# LP_rev1.net
KiCad netlist of a schematic drawn in EAGLE
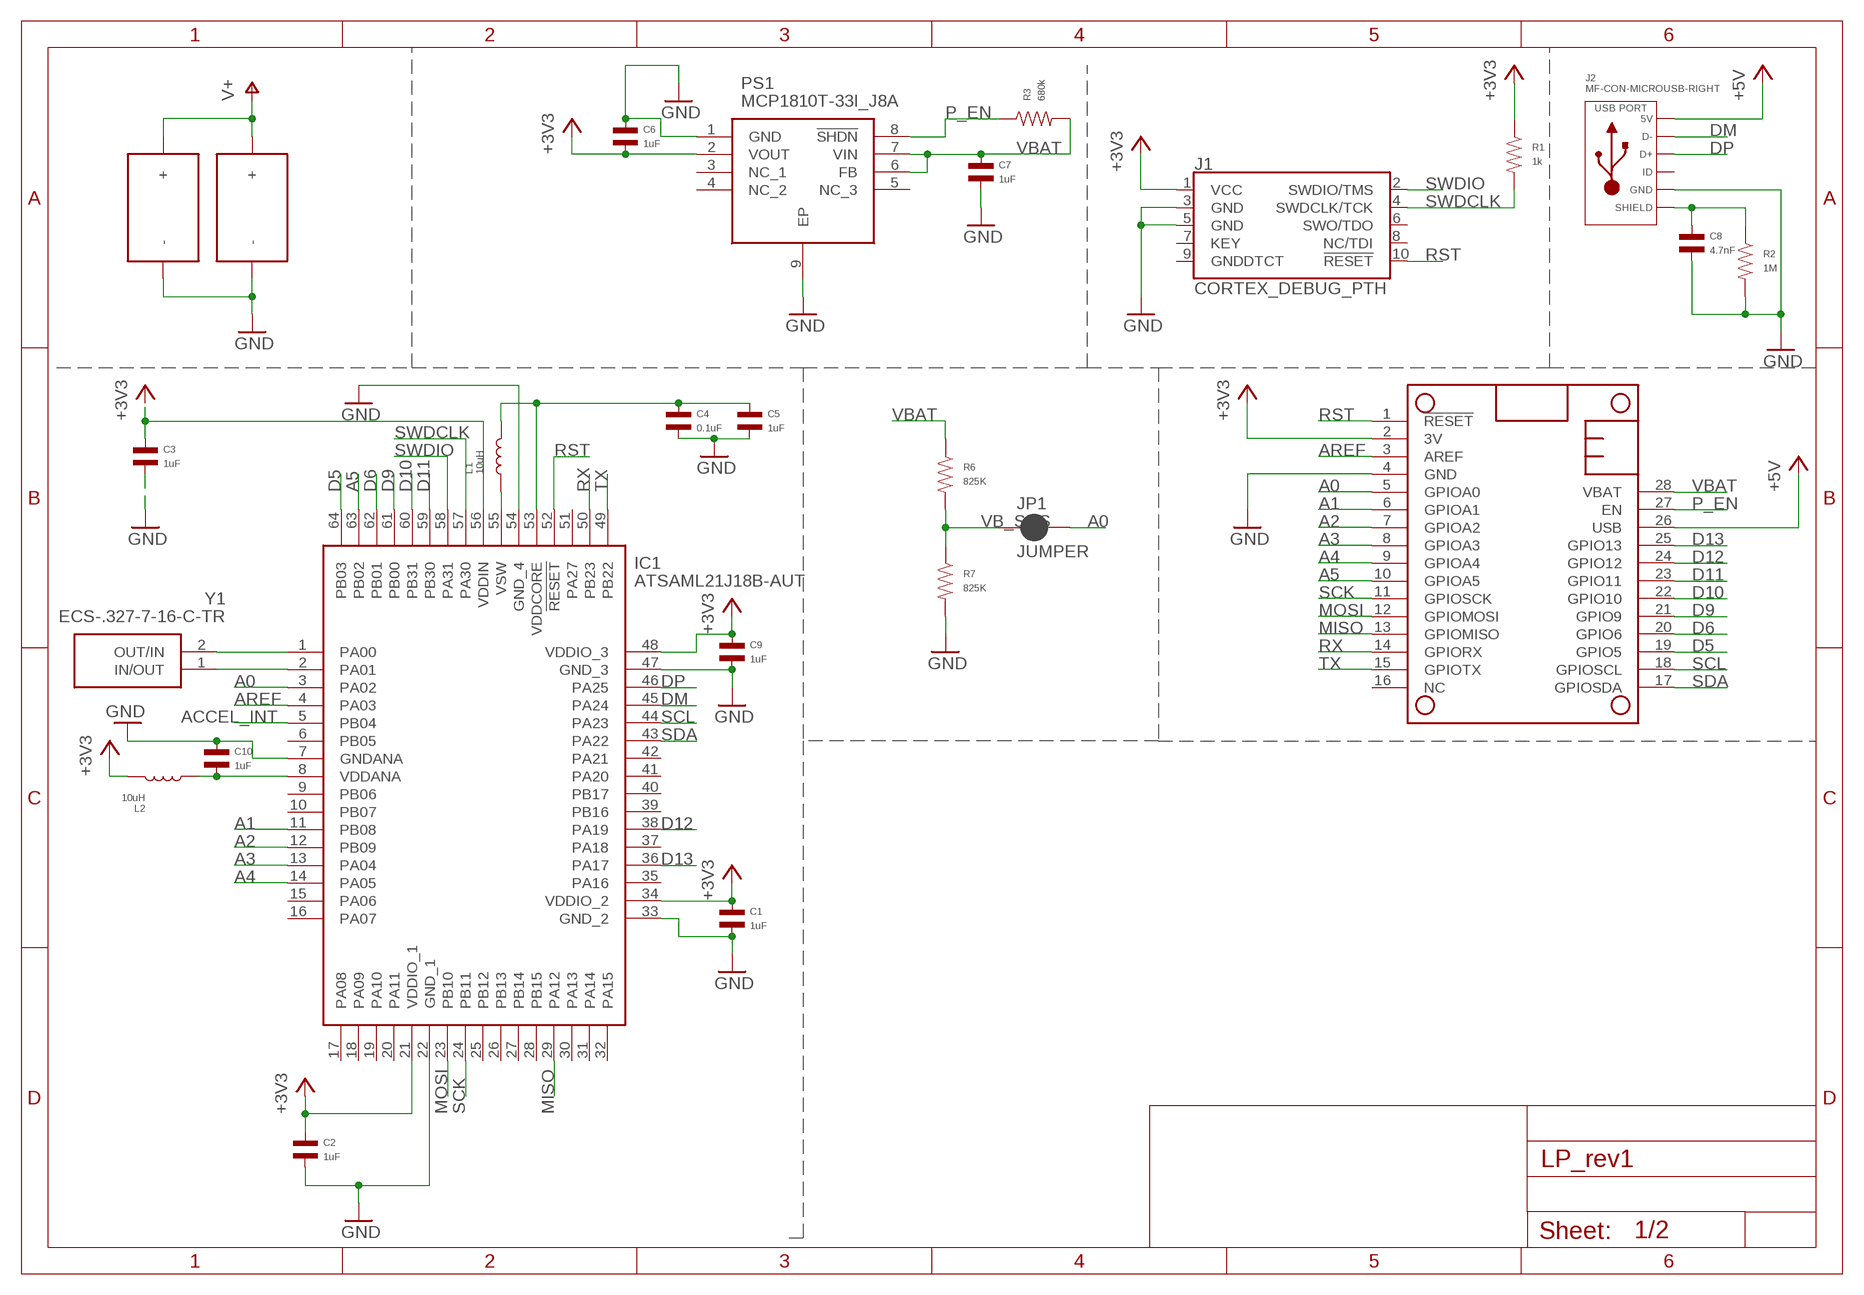
[diagram p0: schematic, sheet 1]
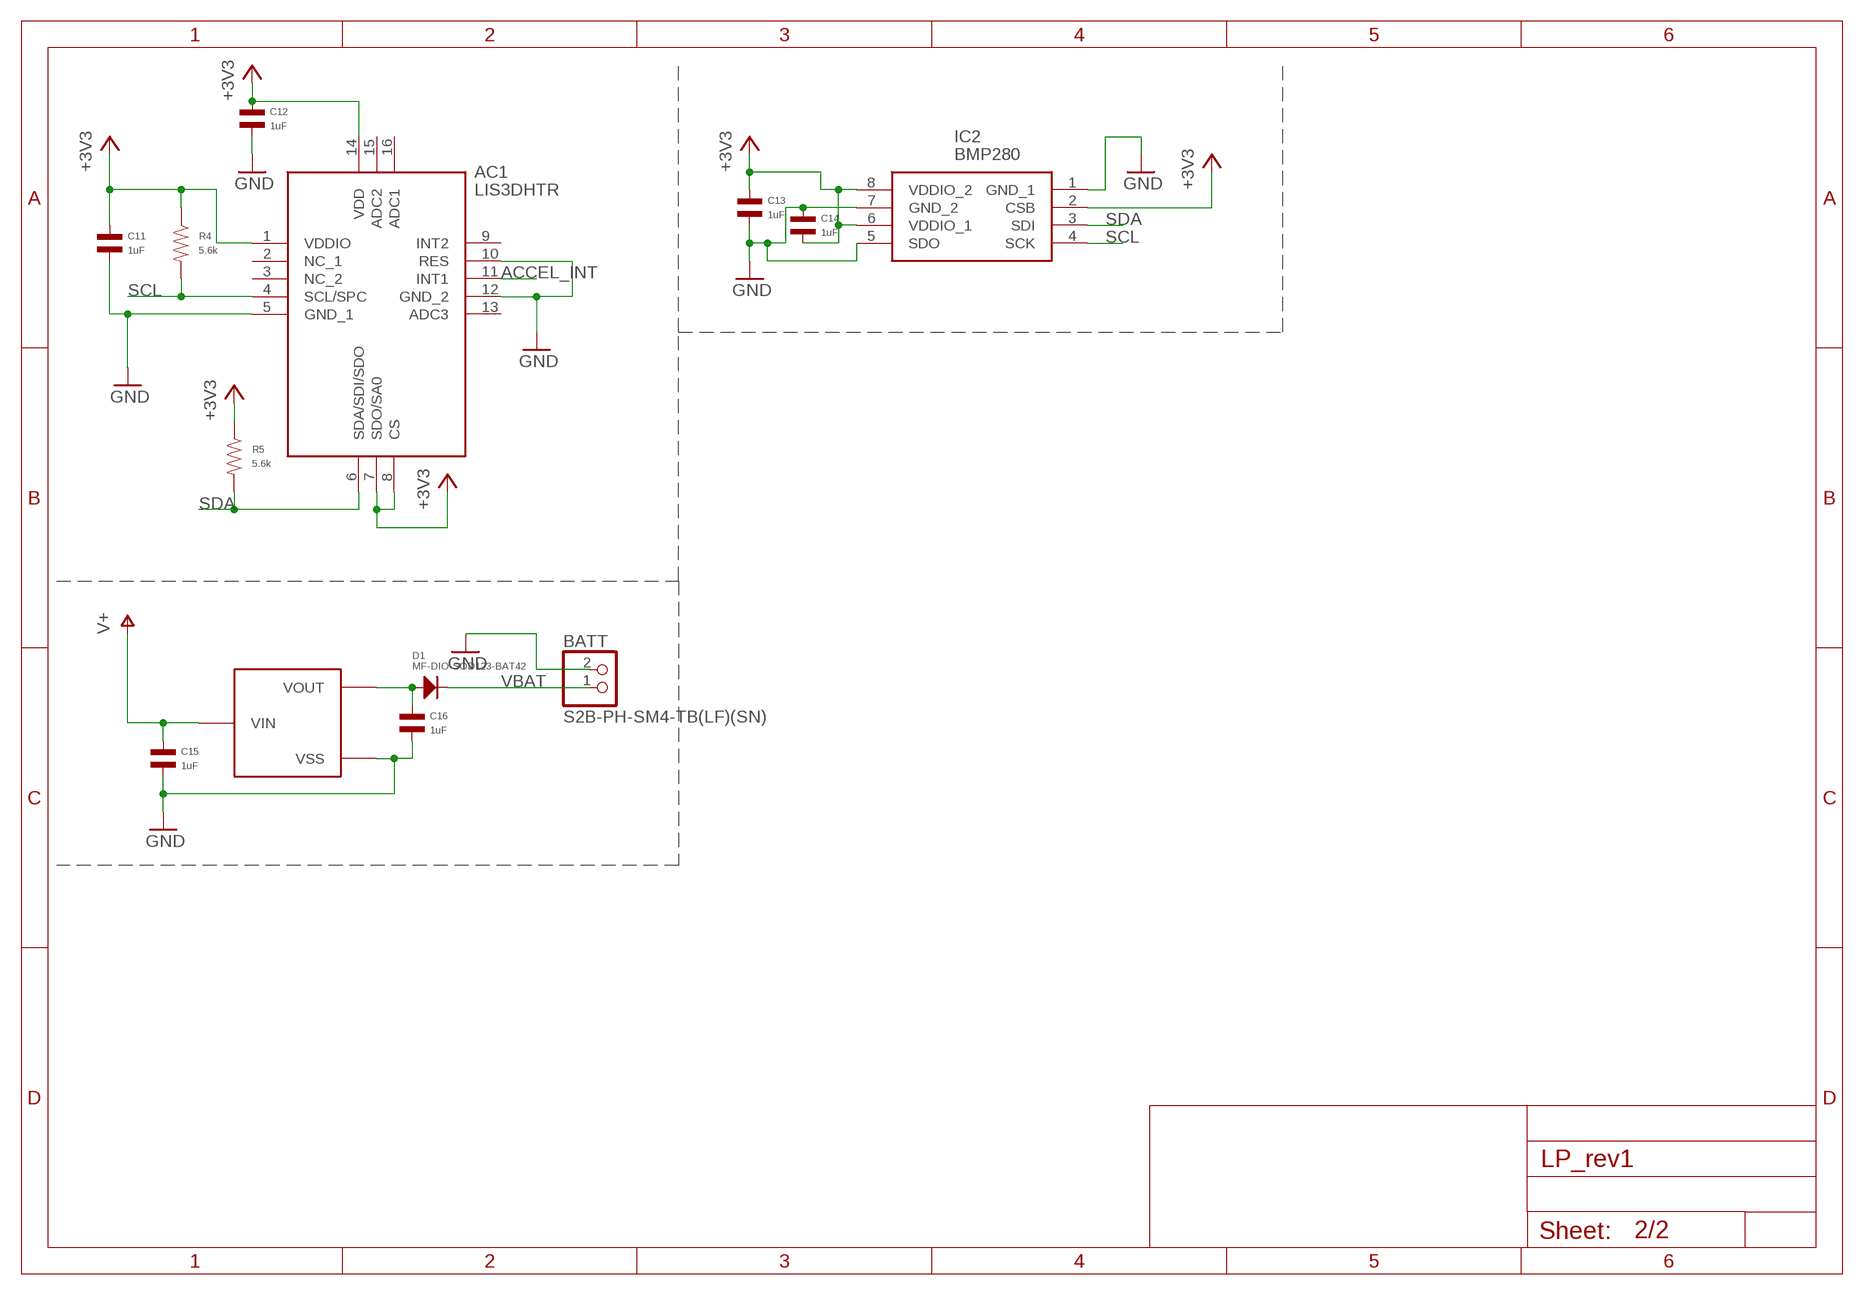
[diagram p1: schematic, sheet 2]

(export (version "E")
  (design (tool "Eeschema 10.0.6"))
  (components
    (comp (ref "AC1")
      (value "LIS3DHTR")
      (footprint "eagle-import:PQFN50P300X300X100-16N")
      (fields (field (name "MOUSER_PART_NUMBER") "511-LIS3DHTR") (field (name "RS_PART_NUMBER") "7931364P"))
      (libsource (lib "eagle-import") (part "LIS3DHTR"))
    )
    (comp (ref "BATT")
      (value "S2B-PH-SM4-TB(LF)(SN)")
      (footprint "eagle-import:JST-PH-2-SMT-RA")
      (libsource (lib "eagle-import") (part "JST_2PIN-SMT-RA"))
    )
    (comp (ref "C11")
      (value "1uF")
      (footprint "eagle-import:C0402")
      (libsource (lib "eagle-import") (part "CAPACITOR_NP_0402"))
    )
    (comp (ref "C12")
      (value "1uF")
      (footprint "eagle-import:C0402")
      (libsource (lib "eagle-import") (part "CAPACITOR_NP_0402"))
    )
    (comp (ref "C13")
      (value "1uF")
      (footprint "eagle-import:C0402")
      (libsource (lib "eagle-import") (part "CAPACITOR_NP_0402"))
    )
    (comp (ref "C14")
      (value "1uF")
      (footprint "eagle-import:C0402")
      (libsource (lib "eagle-import") (part "CAPACITOR_NP_0402"))
    )
    (comp (ref "C15")
      (value "1uF")
      (footprint "eagle-import:C0402")
      (libsource (lib "eagle-import") (part "CAPACITOR_NP_0402"))
    )
    (comp (ref "C16")
      (value "1uF")
      (footprint "eagle-import:C0402")
      (libsource (lib "eagle-import") (part "CAPACITOR_NP_0402"))
    )
    (comp (ref "D1")
      (value "MF-DIO-SOD123-BAT42")
      (footprint "eagle-import:SOD-123")
      (fields (field (name "HOUSEPART") "YES"))
      (libsource (lib "eagle-import") (part "DIODES_SOD-123_BAT42"))
    )
    (comp (ref "IC2")
      (value "BMP280")
      (footprint "eagle-import:8-PIN-METAL-LID-LGA")
      (fields
        (field (name "MANUFACTURER_PART_NUMBER") "bmp280")
        (field (name "MOUSER_PART_NUMBER") "262-BMP280")
      )
      (libsource (lib "eagle-import") (part "BMP280"))
    )
    (comp (ref "R4")
      (value "5.6k")
      (footprint "eagle-import:R0402")
      (libsource (lib "eagle-import") (part "RESISTOR_0402"))
    )
    (comp (ref "R5")
      (value "5.6k")
      (footprint "eagle-import:R0402")
      (libsource (lib "eagle-import") (part "RESISTOR_0402"))
    )
    (comp (ref "U$3")
      (value "XC6206P422MR-G")
      (footprint "eagle-import:XC6206")
      (libsource (lib "eagle-import") (part "XC6206"))
    )
    (comp (ref "C1")
      (value "1uF")
      (footprint "eagle-import:C0402")
      (libsource (lib "eagle-import") (part "CAPACITOR_NP_0402"))
    )
    (comp (ref "C2")
      (value "1uF")
      (footprint "eagle-import:C0402")
      (libsource (lib "eagle-import") (part "CAPACITOR_NP_0402"))
    )
    (comp (ref "C3")
      (value "1uF")
      (footprint "eagle-import:C0402")
      (libsource (lib "eagle-import") (part "CAPACITOR_NP_0402"))
    )
    (comp (ref "C4")
      (value "0.1uF")
      (footprint "eagle-import:C0402")
      (libsource (lib "eagle-import") (part "CAPACITOR_NP_0402"))
    )
    (comp (ref "C5")
      (value "1uF")
      (footprint "eagle-import:C0402")
      (libsource (lib "eagle-import") (part "CAPACITOR_NP_0402"))
    )
    (comp (ref "C6")
      (value "1uF")
      (footprint "eagle-import:C0402")
      (libsource (lib "eagle-import") (part "CAPACITOR_NP_0402"))
    )
    (comp (ref "C7")
      (value "1uF")
      (footprint "eagle-import:C0402")
      (libsource (lib "eagle-import") (part "CAPACITOR_NP_0402"))
    )
    (comp (ref "C8")
      (value "4.7nF")
      (footprint "eagle-import:C0402")
      (libsource (lib "eagle-import") (part "CAPACITOR_NP_0402"))
    )
    (comp (ref "C9")
      (value "1uF")
      (footprint "eagle-import:C0402")
      (libsource (lib "eagle-import") (part "CAPACITOR_NP_0402"))
    )
    (comp (ref "C10")
      (value "1uF")
      (footprint "eagle-import:C0402")
      (libsource (lib "eagle-import") (part "CAPACITOR_NP_0402"))
    )
    (comp (ref "IC1")
      (value "ATSAML21J18B-AUT")
      (footprint "eagle-import:QFP50P1200X1200X120-64N")
      (fields (field (name "MOUSER_PART_NUMBER") "556-ATSAML21J18B-AUT"))
      (libsource (lib "eagle-import") (part "ATSAML21J18B-AUT"))
    )
    (comp (ref "J1")
      (value "CORTEX_DEBUG_PTH")
      (footprint "eagle-import:2X5-PTH-1.27MM")
      (libsource (lib "eagle-import") (part "CORTEX_DEBUG_PTH"))
    )
    (comp (ref "J2")
      (value "MF-CON-MICROUSB-RIGHT")
      (footprint "eagle-import:MICROUSB-RIGHT")
      (fields (field (name "HOUSEPART") "YES"))
      (libsource (lib "eagle-import") (part "USB_MICRO_RIGHT"))
    )
    (comp (ref "JP1")
      (value "JUMPER")
      (footprint "eagle-import:SMT-JUMPER_2_NC_PASTE_NO-SILK")
      (libsource (lib "eagle-import") (part "JUMPER-SMT_2_NC_PASTE_NO-SILK"))
    )
    (comp (ref "L1")
      (value "10uH")
      (footprint "eagle-import:L0603")
      (libsource (lib "eagle-import") (part "INDUCTOR_0603"))
    )
    (comp (ref "L2")
      (value "10uH")
      (footprint "eagle-import:L0603")
      (libsource (lib "eagle-import") (part "INDUCTOR_0603"))
    )
    (comp (ref "MS1")
      (value "FEATHERWING")
      (footprint "eagle-import:FEATHERWING")
      (libsource (lib "eagle-import") (part "FEATHERWING"))
    )
    (comp (ref "PS1")
      (value "MCP1810T-33I_J8A")
      (footprint "eagle-import:SON50P200X200X90-9N")
      (fields
        (field (name "MANUFACTURER_PART_NUMBER") "MCP1810T-33I/J8A")
        (field (name "MOUSER_PART_NUMBER") "579-MCP1810T-33I/J8A")
        (field (name "RS_PART_NUMBER") "1468894P")
      )
      (libsource (lib "eagle-import") (part "MCP1810T-33I_J8A"))
    )
    (comp (ref "R1")
      (value "1k")
      (footprint "eagle-import:R0402")
      (libsource (lib "eagle-import") (part "RESISTOR_0402"))
    )
    (comp (ref "R2")
      (value "1M")
      (footprint "eagle-import:R0402")
      (libsource (lib "eagle-import") (part "RESISTOR_0402"))
    )
    (comp (ref "R3")
      (value "680k")
      (footprint "eagle-import:R0402")
      (libsource (lib "eagle-import") (part "RESISTOR_0402"))
    )
    (comp (ref "R6")
      (value "825K")
      (footprint "eagle-import:R0402")
      (libsource (lib "eagle-import") (part "RESISTOR_0402"))
    )
    (comp (ref "R7")
      (value "825K")
      (footprint "eagle-import:R0402")
      (libsource (lib "eagle-import") (part "RESISTOR_0402"))
    )
    (comp (ref "U$1")
      (value "KXOB25-01X8F")
      (footprint "eagle-import:KXOB25-01X8F")
      (libsource (lib "eagle-import") (part "KXOB25-01X8F"))
    )
    (comp (ref "U$2")
      (value "KXOB25-01X8F")
      (footprint "eagle-import:KXOB25-01X8F")
      (libsource (lib "eagle-import") (part "KXOB25-01X8F"))
    )
    (comp (ref "Y1")
      (value "ECS-.327-7-16-C-TR")
      (footprint "eagle-import:ECS327516TR")
      (fields (field (name "MOUSER_PART_NUMBER") "520-.327-7-16-CT"))
      (libsource (lib "eagle-import") (part "ECS-.327-7-16-C-TR"))
    )
  )
  (nets
    (net (code "1") (name "+3V3") (class "Default")
      (node (ref "AC1") (pin "1") (pinfunction "VDDIO_1") (pintype "power_in"))
      (node (ref "AC1") (pin "14") (pinfunction "VDD_14") (pintype "power_in"))
      (node (ref "AC1") (pin "7") (pinfunction "SDO/SA0_7") (pintype "bidirectional"))
      (node (ref "AC1") (pin "8") (pinfunction "CS_8") (pintype "input"))
      (node (ref "C1") (pin "P$1") (pinfunction "P$1_P$1") (pintype "passive"))
      (node (ref "C11") (pin "P$1") (pinfunction "P$1_P$1") (pintype "passive"))
      (node (ref "C12") (pin "P$1") (pinfunction "P$1_P$1") (pintype "passive"))
      (node (ref "C13") (pin "P$1") (pinfunction "P$1_P$1") (pintype "passive"))
      (node (ref "C14") (pin "P$2") (pinfunction "P$2_P$2") (pintype "passive"))
      (node (ref "C2") (pin "P$1") (pinfunction "P$1_P$1") (pintype "passive"))
      (node (ref "C3") (pin "P$1") (pinfunction "P$1_P$1") (pintype "passive"))
      (node (ref "C6") (pin "P$2") (pinfunction "P$2_P$2") (pintype "passive"))
      (node (ref "C9") (pin "P$1") (pinfunction "P$1_P$1") (pintype "passive"))
      (node (ref "IC1") (pin "21") (pinfunction "VDDIO_1_21") (pintype "bidirectional"))
      (node (ref "IC1") (pin "34") (pinfunction "VDDIO_2_34") (pintype "bidirectional"))
      (node (ref "IC1") (pin "48") (pinfunction "VDDIO_3_48") (pintype "bidirectional"))
      (node (ref "IC1") (pin "56") (pinfunction "VDDIN_56") (pintype "bidirectional"))
      (node (ref "IC2") (pin "2") (pinfunction "CSB_2") (pintype "input"))
      (node (ref "IC2") (pin "6") (pinfunction "VDDIO_1_6") (pintype "power_in"))
      (node (ref "IC2") (pin "8") (pinfunction "VDDIO_2_8") (pintype "power_in"))
      (node (ref "J1") (pin "1") (pinfunction "VCC_1") (pintype "bidirectional"))
      (node (ref "L2") (pin "P$2") (pinfunction "P$2_P$2") (pintype "passive"))
      (node (ref "MS1") (pin "2") (pinfunction "3V_2") (pintype "power_in"))
      (node (ref "PS1") (pin "2") (pinfunction "VOUT_2") (pintype "output"))
      (node (ref "R1") (pin "P$1") (pinfunction "P$1_P$1") (pintype "passive"))
      (node (ref "R4") (pin "P$1") (pinfunction "P$1_P$1") (pintype "passive"))
      (node (ref "R5") (pin "P$1") (pinfunction "P$1_P$1") (pintype "passive"))
    )
    (net (code "2") (name "+5V") (class "Default")
      (node (ref "J2") (pin "1") (pinfunction "5V_1") (pintype "power_in"))
      (node (ref "MS1") (pin "26") (pinfunction "USB_26") (pintype "power_in"))
    )
    (net (code "3") (name "A0") (class "Default")
      (node (ref "IC1") (pin "3") (pinfunction "PA02_3") (pintype "bidirectional"))
      (node (ref "JP1") (pin "2") (pinfunction "2_2") (pintype "passive"))
      (node (ref "MS1") (pin "5") (pinfunction "GPIOA0_5") (pintype "bidirectional"))
    )
    (net (code "4") (name "A1") (class "Default")
      (node (ref "IC1") (pin "11") (pinfunction "PB08_11") (pintype "bidirectional"))
      (node (ref "MS1") (pin "6") (pinfunction "GPIOA1_6") (pintype "bidirectional"))
    )
    (net (code "5") (name "A2") (class "Default")
      (node (ref "IC1") (pin "12") (pinfunction "PB09_12") (pintype "bidirectional"))
      (node (ref "MS1") (pin "7") (pinfunction "GPIOA2_7") (pintype "bidirectional"))
    )
    (net (code "6") (name "A3") (class "Default")
      (node (ref "IC1") (pin "13") (pinfunction "PA04_13") (pintype "bidirectional"))
      (node (ref "MS1") (pin "8") (pinfunction "GPIOA3_8") (pintype "bidirectional"))
    )
    (net (code "7") (name "A4") (class "Default")
      (node (ref "IC1") (pin "14") (pinfunction "PA05_14") (pintype "bidirectional"))
      (node (ref "MS1") (pin "9") (pinfunction "GPIOA4_9") (pintype "bidirectional"))
    )
    (net (code "8") (name "A5") (class "Default")
      (node (ref "IC1") (pin "63") (pinfunction "PB02_63") (pintype "bidirectional"))
      (node (ref "MS1") (pin "10") (pinfunction "GPIOA5_10") (pintype "bidirectional"))
    )
    (net (code "9") (name "ACCEL_INT") (class "Default")
      (node (ref "AC1") (pin "11") (pinfunction "INT1_11") (pintype "input"))
      (node (ref "IC1") (pin "5") (pinfunction "PB04_5") (pintype "bidirectional"))
    )
    (net (code "10") (name "AREF") (class "Default")
      (node (ref "IC1") (pin "4") (pinfunction "PA03_4") (pintype "bidirectional"))
      (node (ref "MS1") (pin "3") (pinfunction "AREF_3") (pintype "passive"))
    )
    (net (code "11") (name "D5") (class "Default")
      (node (ref "IC1") (pin "64") (pinfunction "PB03_64") (pintype "bidirectional"))
      (node (ref "MS1") (pin "19") (pinfunction "GPIO5_19") (pintype "bidirectional"))
    )
    (net (code "12") (name "D6") (class "Default")
      (node (ref "IC1") (pin "62") (pinfunction "PB01_62") (pintype "bidirectional"))
      (node (ref "MS1") (pin "20") (pinfunction "GPIO6_20") (pintype "bidirectional"))
    )
    (net (code "13") (name "D9") (class "Default")
      (node (ref "IC1") (pin "61") (pinfunction "PB00_61") (pintype "bidirectional"))
      (node (ref "MS1") (pin "21") (pinfunction "GPIO9_21") (pintype "bidirectional"))
    )
    (net (code "14") (name "D10") (class "Default")
      (node (ref "IC1") (pin "60") (pinfunction "PB31_60") (pintype "bidirectional"))
      (node (ref "MS1") (pin "22") (pinfunction "GPIO10_22") (pintype "bidirectional"))
    )
    (net (code "15") (name "D11") (class "Default")
      (node (ref "IC1") (pin "59") (pinfunction "PB30_59") (pintype "bidirectional"))
      (node (ref "MS1") (pin "23") (pinfunction "GPIO11_23") (pintype "bidirectional"))
    )
    (net (code "16") (name "D12") (class "Default")
      (node (ref "IC1") (pin "38") (pinfunction "PA19_38") (pintype "bidirectional"))
      (node (ref "MS1") (pin "24") (pinfunction "GPIO12_24") (pintype "bidirectional"))
    )
    (net (code "17") (name "D13") (class "Default")
      (node (ref "IC1") (pin "36") (pinfunction "PA17_36") (pintype "bidirectional"))
      (node (ref "MS1") (pin "25") (pinfunction "GPIO13_25") (pintype "bidirectional"))
    )
    (net (code "18") (name "DM") (class "Default")
      (node (ref "IC1") (pin "45") (pinfunction "PA24_45") (pintype "bidirectional"))
      (node (ref "J2") (pin "2") (pinfunction "D-_2") (pintype "bidirectional"))
    )
    (net (code "19") (name "DP") (class "Default")
      (node (ref "IC1") (pin "46") (pinfunction "PA25_46") (pintype "bidirectional"))
      (node (ref "J2") (pin "3") (pinfunction "D+_3") (pintype "bidirectional"))
    )
    (net (code "20") (name "GND") (class "Default")
      (node (ref "AC1") (pin "10") (pinfunction "RES_10") (pintype "bidirectional"))
      (node (ref "AC1") (pin "12") (pinfunction "GND_2_12") (pintype "power_in"))
      (node (ref "AC1") (pin "5") (pinfunction "GND_1_5") (pintype "power_in"))
      (node (ref "BATT") (pin "2") (pinfunction "1_2") (pintype "passive"))
      (node (ref "C1") (pin "P$2") (pinfunction "P$2_P$2") (pintype "passive"))
      (node (ref "C10") (pin "P$1") (pinfunction "P$1_P$1") (pintype "passive"))
      (node (ref "C11") (pin "P$2") (pinfunction "P$2_P$2") (pintype "passive"))
      (node (ref "C12") (pin "P$2") (pinfunction "P$2_P$2") (pintype "passive"))
      (node (ref "C13") (pin "P$2") (pinfunction "P$2_P$2") (pintype "passive"))
      (node (ref "C14") (pin "P$1") (pinfunction "P$1_P$1") (pintype "passive"))
      (node (ref "C15") (pin "P$2") (pinfunction "P$2_P$2") (pintype "passive"))
      (node (ref "C16") (pin "P$2") (pinfunction "P$2_P$2") (pintype "passive"))
      (node (ref "C2") (pin "P$2") (pinfunction "P$2_P$2") (pintype "passive"))
      (node (ref "C3") (pin "P$2") (pinfunction "P$2_P$2") (pintype "passive"))
      (node (ref "C4") (pin "P$2") (pinfunction "P$2_P$2") (pintype "passive"))
      (node (ref "C5") (pin "P$2") (pinfunction "P$2_P$2") (pintype "passive"))
      (node (ref "C6") (pin "P$1") (pinfunction "P$1_P$1") (pintype "passive"))
      (node (ref "C7") (pin "P$2") (pinfunction "P$2_P$2") (pintype "passive"))
      (node (ref "C8") (pin "P$2") (pinfunction "P$2_P$2") (pintype "passive"))
      (node (ref "C9") (pin "P$2") (pinfunction "P$2_P$2") (pintype "passive"))
      (node (ref "IC1") (pin "22") (pinfunction "GND_1_22") (pintype "bidirectional"))
      (node (ref "IC1") (pin "33") (pinfunction "GND_2_33") (pintype "bidirectional"))
      (node (ref "IC1") (pin "47") (pinfunction "GND_3_47") (pintype "bidirectional"))
      (node (ref "IC1") (pin "54") (pinfunction "GND_4_54") (pintype "bidirectional"))
      (node (ref "IC1") (pin "7") (pinfunction "GNDANA_7") (pintype "bidirectional"))
      (node (ref "IC2") (pin "1") (pinfunction "GND_1_1") (pintype "power_in"))
      (node (ref "IC2") (pin "5") (pinfunction "SDO_5") (pintype "bidirectional"))
      (node (ref "IC2") (pin "7") (pinfunction "GND_2_7") (pintype "power_in"))
      (node (ref "J1") (pin "3") (pinfunction "GND_3") (pintype "bidirectional"))
      (node (ref "J1") (pin "5") (pinfunction "GND_5") (pintype "bidirectional"))
      (node (ref "J2") (pin "5") (pinfunction "GND_5") (pintype "power_in"))
      (node (ref "MS1") (pin "4") (pinfunction "GND_4") (pintype "power_in"))
      (node (ref "PS1") (pin "1") (pinfunction "GND_1") (pintype "power_in"))
      (node (ref "PS1") (pin "9") (pinfunction "EP_9") (pintype "power_in"))
      (node (ref "R2") (pin "P$2") (pinfunction "P$2_P$2") (pintype "passive"))
      (node (ref "R7") (pin "P$2") (pinfunction "P$2_P$2") (pintype "passive"))
      (node (ref "U$1") (pin "P$2") (pinfunction "-_P$2") (pintype "bidirectional"))
      (node (ref "U$2") (pin "P$2") (pinfunction "-_P$2") (pintype "bidirectional"))
      (node (ref "U$3") (pin "P$1") (pinfunction "VSS_P$1") (pintype "bidirectional"))
    )
    (net (code "21") (name "MISO") (class "Default")
      (node (ref "IC1") (pin "29") (pinfunction "PA12_29") (pintype "bidirectional"))
      (node (ref "MS1") (pin "13") (pinfunction "GPIOMISO_13") (pintype "bidirectional"))
    )
    (net (code "22") (name "MOSI") (class "Default")
      (node (ref "IC1") (pin "23") (pinfunction "PB10_23") (pintype "bidirectional"))
      (node (ref "MS1") (pin "12") (pinfunction "GPIOMOSI_12") (pintype "bidirectional"))
    )
    (net (code "23") (name "Net-(C8-PadP$1)") (class "Default")
      (node (ref "C8") (pin "P$1") (pinfunction "P$1_P$1") (pintype "passive"))
      (node (ref "J2") (pin "S1") (pinfunction "SLD_S1") (pintype "power_in"))
      (node (ref "J2") (pin "S2") (pinfunction "SLD_S2") (pintype "power_in"))
      (node (ref "J2") (pin "S3") (pinfunction "SLD_S3") (pintype "power_in"))
      (node (ref "J2") (pin "S4") (pinfunction "SLD_S4") (pintype "power_in"))
      (node (ref "J2") (pin "S5") (pinfunction "SLD_S5") (pintype "power_in"))
      (node (ref "J2") (pin "S6") (pinfunction "SLD_S6") (pintype "power_in"))
      (node (ref "R2") (pin "P$1") (pinfunction "P$1_P$1") (pintype "passive"))
    )
    (net (code "24") (name "Net-(IC1-PA00)") (class "Default")
      (node (ref "IC1") (pin "1") (pinfunction "PA00_1") (pintype "bidirectional"))
      (node (ref "Y1") (pin "2") (pinfunction "OUT/IN_2") (pintype "bidirectional"))
    )
    (net (code "25") (name "Net-(IC1-PA01)") (class "Default")
      (node (ref "IC1") (pin "2") (pinfunction "PA01_2") (pintype "bidirectional"))
      (node (ref "Y1") (pin "1") (pinfunction "IN/OUT_1") (pintype "bidirectional"))
    )
    (net (code "26") (name "Net-(IC1-VDDANA)") (class "Default")
      (node (ref "C10") (pin "P$2") (pinfunction "P$2_P$2") (pintype "passive"))
      (node (ref "IC1") (pin "8") (pinfunction "VDDANA_8") (pintype "bidirectional"))
      (node (ref "L2") (pin "P$1") (pinfunction "P$1_P$1") (pintype "passive"))
    )
    (net (code "27") (name "Net-(IC1-VDDCORE)") (class "Default")
      (node (ref "C4") (pin "P$1") (pinfunction "P$1_P$1") (pintype "passive"))
      (node (ref "C5") (pin "P$1") (pinfunction "P$1_P$1") (pintype "passive"))
      (node (ref "IC1") (pin "53") (pinfunction "VDDCORE_53") (pintype "bidirectional"))
      (node (ref "L1") (pin "P$2") (pinfunction "P$2_P$2") (pintype "passive"))
    )
    (net (code "28") (name "Net-(IC1-VSW)") (class "Default")
      (node (ref "IC1") (pin "55") (pinfunction "VSW_55") (pintype "bidirectional"))
      (node (ref "L1") (pin "P$1") (pinfunction "P$1_P$1") (pintype "passive"))
    )
    (net (code "29") (name "Net-(U$3-VOUT)") (class "Default")
      (node (ref "C16") (pin "P$1") (pinfunction "P$1_P$1") (pintype "passive"))
      (node (ref "D1") (pin "ANODE") (pinfunction "ANODE_ANODE") (pintype "bidirectional"))
      (node (ref "U$3") (pin "P$2") (pinfunction "VOUT_P$2") (pintype "bidirectional"))
    )
    (net (code "30") (name "P_EN") (class "Default")
      (node (ref "MS1") (pin "27") (pinfunction "EN_27") (pintype "passive"))
      (node (ref "PS1") (pin "8") (pinfunction "~{SHDN}_8") (pintype "input"))
      (node (ref "R3") (pin "P$1") (pinfunction "P$1_P$1") (pintype "passive"))
    )
    (net (code "31") (name "RST") (class "Default")
      (node (ref "IC1") (pin "52") (pinfunction "~{RESET}_52") (pintype "bidirectional"))
      (node (ref "J1") (pin "10") (pinfunction "~{RESET}_10") (pintype "bidirectional"))
      (node (ref "MS1") (pin "1") (pinfunction "~{RESET}_1") (pintype "input"))
    )
    (net (code "32") (name "RX") (class "Default")
      (node (ref "IC1") (pin "50") (pinfunction "PB23_50") (pintype "bidirectional"))
      (node (ref "MS1") (pin "14") (pinfunction "GPIORX_14") (pintype "bidirectional"))
    )
    (net (code "33") (name "SCK") (class "Default")
      (node (ref "IC1") (pin "24") (pinfunction "PB11_24") (pintype "bidirectional"))
      (node (ref "MS1") (pin "11") (pinfunction "GPIOSCK_11") (pintype "bidirectional"))
    )
    (net (code "34") (name "SCL") (class "Default")
      (node (ref "AC1") (pin "4") (pinfunction "SCL/SPC_4") (pintype "bidirectional"))
      (node (ref "IC1") (pin "44") (pinfunction "PA23_44") (pintype "bidirectional"))
      (node (ref "IC2") (pin "4") (pinfunction "SCK_4") (pintype "bidirectional"))
      (node (ref "MS1") (pin "18") (pinfunction "GPIOSCL_18") (pintype "bidirectional"))
      (node (ref "R4") (pin "P$2") (pinfunction "P$2_P$2") (pintype "passive"))
    )
    (net (code "35") (name "SDA") (class "Default")
      (node (ref "AC1") (pin "6") (pinfunction "SDA/SDI/SDO_6") (pintype "bidirectional"))
      (node (ref "IC1") (pin "43") (pinfunction "PA22_43") (pintype "bidirectional"))
      (node (ref "IC2") (pin "3") (pinfunction "SDI_3") (pintype "bidirectional"))
      (node (ref "MS1") (pin "17") (pinfunction "GPIOSDA_17") (pintype "bidirectional"))
      (node (ref "R5") (pin "P$2") (pinfunction "P$2_P$2") (pintype "passive"))
    )
    (net (code "36") (name "SWDCLK") (class "Default")
      (node (ref "IC1") (pin "57") (pinfunction "PA30_57") (pintype "bidirectional"))
      (node (ref "J1") (pin "4") (pinfunction "SWDCLK/TCK_4") (pintype "bidirectional"))
      (node (ref "R1") (pin "P$2") (pinfunction "P$2_P$2") (pintype "passive"))
    )
    (net (code "37") (name "SWDIO") (class "Default")
      (node (ref "IC1") (pin "58") (pinfunction "PA31_58") (pintype "bidirectional"))
      (node (ref "J1") (pin "2") (pinfunction "SWDIO/TMS_2") (pintype "bidirectional"))
    )
    (net (code "38") (name "TX") (class "Default")
      (node (ref "IC1") (pin "49") (pinfunction "PB22_49") (pintype "bidirectional"))
      (node (ref "MS1") (pin "15") (pinfunction "GPIOTX_15") (pintype "bidirectional"))
    )
    (net (code "39") (name "V+") (class "Default")
      (node (ref "C15") (pin "P$1") (pinfunction "P$1_P$1") (pintype "passive"))
      (node (ref "U$1") (pin "P$1") (pinfunction "+_P$1") (pintype "bidirectional"))
      (node (ref "U$2") (pin "P$1") (pinfunction "+_P$1") (pintype "bidirectional"))
      (node (ref "U$3") (pin "P$3") (pinfunction "VIN_P$3") (pintype "bidirectional"))
    )
    (net (code "40") (name "VBAT") (class "Default")
      (node (ref "BATT") (pin "1") (pinfunction "2_1") (pintype "passive"))
      (node (ref "C7") (pin "P$1") (pinfunction "P$1_P$1") (pintype "passive"))
      (node (ref "D1") (pin "CATHODE") (pinfunction "CATHODE_CATHODE") (pintype "bidirectional"))
      (node (ref "MS1") (pin "28") (pinfunction "VBAT_28") (pintype "power_in"))
      (node (ref "PS1") (pin "6") (pinfunction "FB_6") (pintype "input"))
      (node (ref "PS1") (pin "7") (pinfunction "VIN_7") (pintype "input"))
      (node (ref "R3") (pin "P$2") (pinfunction "P$2_P$2") (pintype "passive"))
      (node (ref "R6") (pin "P$1") (pinfunction "P$1_P$1") (pintype "passive"))
    )
    (net (code "41") (name "VB_SNS") (class "Default")
      (node (ref "JP1") (pin "1") (pinfunction "1_1") (pintype "passive"))
      (node (ref "R6") (pin "P$2") (pinfunction "P$2_P$2") (pintype "passive"))
      (node (ref "R7") (pin "P$1") (pinfunction "P$1_P$1") (pintype "passive"))
    )
    (net (code "42") (name "unconnected-(AC1-ADC1-Pad16)") (class "Default")
      (node (ref "AC1") (pin "16") (pinfunction "ADC1_16") (pintype "bidirectional"))
    )
    (net (code "43") (name "unconnected-(AC1-ADC2-Pad15)") (class "Default")
      (node (ref "AC1") (pin "15") (pinfunction "ADC2_15") (pintype "bidirectional"))
    )
    (net (code "44") (name "unconnected-(AC1-ADC3-Pad13)") (class "Default")
      (node (ref "AC1") (pin "13") (pinfunction "ADC3_13") (pintype "bidirectional"))
    )
    (net (code "45") (name "unconnected-(AC1-INT2-Pad9)") (class "Default")
      (node (ref "AC1") (pin "9") (pinfunction "INT2_9") (pintype "input"))
    )
    (net (code "46") (name "unconnected-(AC1-NC_1-Pad2)") (class "Default")
      (node (ref "AC1") (pin "2") (pinfunction "NC_1_2") (pintype "bidirectional"))
    )
    (net (code "47") (name "unconnected-(AC1-NC_2-Pad3)") (class "Default")
      (node (ref "AC1") (pin "3") (pinfunction "NC_2_3") (pintype "bidirectional"))
    )
    (net (code "48") (name "unconnected-(IC1-PA06-Pad15)") (class "Default")
      (node (ref "IC1") (pin "15") (pinfunction "PA06_15") (pintype "bidirectional"))
    )
    (net (code "49") (name "unconnected-(IC1-PA07-Pad16)") (class "Default")
      (node (ref "IC1") (pin "16") (pinfunction "PA07_16") (pintype "bidirectional"))
    )
    (net (code "50") (name "unconnected-(IC1-PA08-Pad17)") (class "Default")
      (node (ref "IC1") (pin "17") (pinfunction "PA08_17") (pintype "bidirectional"))
    )
    (net (code "51") (name "unconnected-(IC1-PA09-Pad18)") (class "Default")
      (node (ref "IC1") (pin "18") (pinfunction "PA09_18") (pintype "bidirectional"))
    )
    (net (code "52") (name "unconnected-(IC1-PA10-Pad19)") (class "Default")
      (node (ref "IC1") (pin "19") (pinfunction "PA10_19") (pintype "bidirectional"))
    )
    (net (code "53") (name "unconnected-(IC1-PA11-Pad20)") (class "Default")
      (node (ref "IC1") (pin "20") (pinfunction "PA11_20") (pintype "bidirectional"))
    )
    (net (code "54") (name "unconnected-(IC1-PA13-Pad30)") (class "Default")
      (node (ref "IC1") (pin "30") (pinfunction "PA13_30") (pintype "bidirectional"))
    )
    (net (code "55") (name "unconnected-(IC1-PA14-Pad31)") (class "Default")
      (node (ref "IC1") (pin "31") (pinfunction "PA14_31") (pintype "bidirectional"))
    )
    (net (code "56") (name "unconnected-(IC1-PA15-Pad32)") (class "Default")
      (node (ref "IC1") (pin "32") (pinfunction "PA15_32") (pintype "bidirectional"))
    )
    (net (code "57") (name "unconnected-(IC1-PA16-Pad35)") (class "Default")
      (node (ref "IC1") (pin "35") (pinfunction "PA16_35") (pintype "bidirectional"))
    )
    (net (code "58") (name "unconnected-(IC1-PA18-Pad37)") (class "Default")
      (node (ref "IC1") (pin "37") (pinfunction "PA18_37") (pintype "bidirectional"))
    )
    (net (code "59") (name "unconnected-(IC1-PA20-Pad41)") (class "Default")
      (node (ref "IC1") (pin "41") (pinfunction "PA20_41") (pintype "bidirectional"))
    )
    (net (code "60") (name "unconnected-(IC1-PA21-Pad42)") (class "Default")
      (node (ref "IC1") (pin "42") (pinfunction "PA21_42") (pintype "bidirectional"))
    )
    (net (code "61") (name "unconnected-(IC1-PA27-Pad51)") (class "Default")
      (node (ref "IC1") (pin "51") (pinfunction "PA27_51") (pintype "bidirectional"))
    )
    (net (code "62") (name "unconnected-(IC1-PB05-Pad6)") (class "Default")
      (node (ref "IC1") (pin "6") (pinfunction "PB05_6") (pintype "bidirectional"))
    )
    (net (code "63") (name "unconnected-(IC1-PB06-Pad9)") (class "Default")
      (node (ref "IC1") (pin "9") (pinfunction "PB06_9") (pintype "bidirectional"))
    )
    (net (code "64") (name "unconnected-(IC1-PB07-Pad10)") (class "Default")
      (node (ref "IC1") (pin "10") (pinfunction "PB07_10") (pintype "bidirectional"))
    )
    (net (code "65") (name "unconnected-(IC1-PB12-Pad25)") (class "Default")
      (node (ref "IC1") (pin "25") (pinfunction "PB12_25") (pintype "bidirectional"))
    )
    (net (code "66") (name "unconnected-(IC1-PB13-Pad26)") (class "Default")
      (node (ref "IC1") (pin "26") (pinfunction "PB13_26") (pintype "bidirectional"))
    )
    (net (code "67") (name "unconnected-(IC1-PB14-Pad27)") (class "Default")
      (node (ref "IC1") (pin "27") (pinfunction "PB14_27") (pintype "bidirectional"))
    )
    (net (code "68") (name "unconnected-(IC1-PB15-Pad28)") (class "Default")
      (node (ref "IC1") (pin "28") (pinfunction "PB15_28") (pintype "bidirectional"))
    )
    (net (code "69") (name "unconnected-(IC1-PB16-Pad39)") (class "Default")
      (node (ref "IC1") (pin "39") (pinfunction "PB16_39") (pintype "bidirectional"))
    )
    (net (code "70") (name "unconnected-(IC1-PB17-Pad40)") (class "Default")
      (node (ref "IC1") (pin "40") (pinfunction "PB17_40") (pintype "bidirectional"))
    )
    (net (code "71") (name "unconnected-(J1-GNDDTCT-Pad9)") (class "Default")
      (node (ref "J1") (pin "9") (pinfunction "GNDDTCT_9") (pintype "bidirectional"))
    )
    (net (code "72") (name "unconnected-(J1-KEY-Pad7)") (class "Default")
      (node (ref "J1") (pin "7") (pinfunction "KEY_7") (pintype "bidirectional"))
    )
    (net (code "73") (name "unconnected-(J1-NC{slash}TDI-Pad8)") (class "Default")
      (node (ref "J1") (pin "8") (pinfunction "NC/TDI_8") (pintype "bidirectional"))
    )
    (net (code "74") (name "unconnected-(J1-SWO{slash}TDO-Pad6)") (class "Default")
      (node (ref "J1") (pin "6") (pinfunction "SWO/TDO_6") (pintype "bidirectional"))
    )
    (net (code "75") (name "unconnected-(J2-ID-Pad4)") (class "Default")
      (node (ref "J2") (pin "4") (pinfunction "ID_4") (pintype "bidirectional"))
    )
    (net (code "76") (name "unconnected-(MS1-NC-Pad16)") (class "Default")
      (node (ref "MS1") (pin "16") (pinfunction "NC_16") (pintype "passive"))
    )
    (net (code "77") (name "unconnected-(PS1-NC_1-Pad3)") (class "Default")
      (node (ref "PS1") (pin "3") (pinfunction "NC_1_3") (pintype "bidirectional"))
    )
    (net (code "78") (name "unconnected-(PS1-NC_2-Pad4)") (class "Default")
      (node (ref "PS1") (pin "4") (pinfunction "NC_2_4") (pintype "bidirectional"))
    )
    (net (code "79") (name "unconnected-(PS1-NC_3-Pad5)") (class "Default")
      (node (ref "PS1") (pin "5") (pinfunction "NC_3_5") (pintype "bidirectional"))
    )
  )
)
